# sensors.net
KiCad netlist of a schematic drawn in Altium Designer
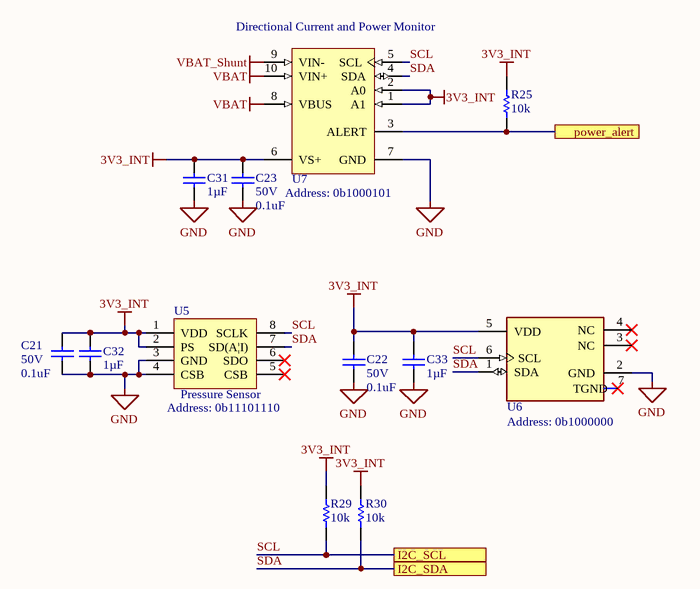
[diagram p0: sensors.SchDoc]

(export (version "E")
  (design (tool "Eeschema 10.0.6"))
  (components
    (comp (ref "C21")
      (value "CL10B104JB8NNNC")
      (footprint "FP-CL10-0_1-MFG")
      (description "CAP CER 0.1UF 50V X7R 0603")
      (fields
        (field (name "TOLERANCE") "5%")
        (field (name "VOLTAGE") "50V")
        (field (name "CAPACITANCE") "0.1uF")
      )
      (libsource (lib "AUVIC") (part "CAP-NP-2"))
    )
    (comp (ref "C22")
      (value "CL10B104JB8NNNC")
      (footprint "FP-CL10-0_1-MFG")
      (description "CAP CER 0.1UF 50V X7R 0603")
      (fields
        (field (name "TOLERANCE") "5%")
        (field (name "VOLTAGE") "50V")
        (field (name "CAPACITANCE") "0.1uF")
      )
      (libsource (lib "AUVIC") (part "CAP-NP-2"))
    )
    (comp (ref "C23")
      (value "CL10B104JB8NNNC")
      (footprint "FP-CL10-0_1-MFG")
      (description "CAP CER 0.1UF 50V X7R 0603")
      (fields
        (field (name "TOLERANCE") "5%")
        (field (name "VOLTAGE") "50V")
        (field (name "CAPACITANCE") "0.1uF")
      )
      (libsource (lib "AUVIC") (part "CAP-NP-2"))
    )
    (comp (ref "C31")
      (value "1µF")
      (footprint "CAPC1608N(0603\")")
      (description "Capacitor, Ceramic, 50V, +/- 10%, 0603 SMD, X5R")
      (fields (field (name "Comment") "1uF 50V 0603 SMD, Ceramic") (field (name "CREATED BY") "Lyden Smith"))
      (libsource (lib "") (part "Symbol_2"))
    )
    (comp (ref "C32")
      (value "1µF")
      (footprint "CAPC1608N(0603\")")
      (description "Capacitor, Ceramic, 50V, +/- 10%, 0603 SMD, X5R")
      (fields (field (name "Comment") "1uF 50V 0603 SMD, Ceramic") (field (name "CREATED BY") "Lyden Smith"))
      (libsource (lib "") (part "Symbol_2"))
    )
    (comp (ref "C33")
      (value "1µF")
      (footprint "CAPC1608N(0603\")")
      (description "Capacitor, Ceramic, 50V, +/- 10%, 0603 SMD, X5R")
      (fields (field (name "Comment") "1uF 50V 0603 SMD, Ceramic") (field (name "CREATED BY") "Lyden Smith"))
      (libsource (lib "") (part "Symbol_2"))
    )
    (comp (ref "R25")
      (value "10k")
      (footprint "RESC1608N(0603\")")
      (description "10kR, 1%, 1/10W, 0603 SMD")
      (fields (field (name "MADE BY") "Ashwin Sira"))
      (libsource (lib "") (part "Symbol_1"))
    )
    (comp (ref "R29")
      (value "10k")
      (footprint "RESC1608N(0603\")")
      (description "10kR, 1%, 1/10W, 0603 SMD")
      (fields (field (name "MADE BY") "Ashwin Sira"))
      (libsource (lib "") (part "Symbol_1"))
    )
    (comp (ref "R30")
      (value "10k")
      (footprint "RESC1608N(0603\")")
      (description "10kR, 1%, 1/10W, 0603 SMD")
      (fields (field (name "MADE BY") "Ashwin Sira"))
      (libsource (lib "") (part "Symbol_1"))
    )
    (comp (ref "U5")
      (value "Pressure Sensor")
      (footprint "TE Pressure Sensor (MS560702BA03-50)")
      (description "1kPa to 120 kPa")
      (fields (field (name "MADE BY") "Andy Bates"))
      (libsource (lib "AUVIC") (part "Symbol"))
    )
    (comp (ref "U6")
      (value "Si700XX")
      (footprint "FP-SI7021-A20-GM1R-IPC_B")
      (description "I2C Humidity and Temperature Sensor")
      (fields (field (name "MADE BY") "Andy Bates"))
      (libsource (lib "AUVIC") (part "36455d3ff5c6bb8356ed7793d24217b"))
    )
    (comp (ref "U7")
      (value "Directional Current and Power Monitor")
      (footprint "DGS0010A_L")
      (description "Bi Directional Current and Power Monitor 10-Pin VSSOP T/R")
      (libsource (lib "AUVIC") (part "TI-INA226DGS10"))
    )
  )
  (nets
    (net (code "1") (name "/SCL") (class "Default")
      (node (ref "R29") (pin "1") (pinfunction "1_1") (pintype "passive"))
      (node (ref "U5") (pin "8") (pinfunction "SCLK_8") (pintype "passive"))
      (node (ref "U6") (pin "6") (pinfunction "SCL_6") (pintype "input"))
      (node (ref "U7") (pin "5") (pinfunction "SCL_5") (pintype "input"))
    )
    (net (code "2") (name "/SDA") (class "Default")
      (node (ref "R30") (pin "1") (pinfunction "1_1") (pintype "passive"))
      (node (ref "U5") (pin "7") (pinfunction "SD(A¦I)_7") (pintype "passive"))
      (node (ref "U6") (pin "1") (pinfunction "SDA_1") (pintype "bidirectional"))
      (node (ref "U7") (pin "4") (pinfunction "SDA_4") (pintype "bidirectional"))
    )
    (net (code "3") (name "/power_alert") (class "Default")
      (node (ref "R25") (pin "1") (pinfunction "1_1") (pintype "passive"))
      (node (ref "U7") (pin "3") (pinfunction "ALERT_3") (pintype "open_collector"))
    )
    (net (code "4") (name "3V3_INT") (class "Default")
      (node (ref "C21") (pin "2") (pinfunction "2_2") (pintype "passive"))
      (node (ref "C22") (pin "2") (pinfunction "2_2") (pintype "passive"))
      (node (ref "C23") (pin "2") (pinfunction "2_2") (pintype "passive"))
      (node (ref "C31") (pin "2") (pinfunction "Cathode_2") (pintype "passive"))
      (node (ref "C32") (pin "2") (pinfunction "Cathode_2") (pintype "passive"))
      (node (ref "C33") (pin "2") (pinfunction "Cathode_2") (pintype "passive"))
      (node (ref "R25") (pin "2") (pinfunction "2_2") (pintype "passive"))
      (node (ref "R29") (pin "2") (pinfunction "2_2") (pintype "passive"))
      (node (ref "R30") (pin "2") (pinfunction "2_2") (pintype "passive"))
      (node (ref "U5") (pin "1") (pinfunction "VDD_1") (pintype "passive"))
      (node (ref "U5") (pin "2") (pinfunction "PS_2") (pintype "passive"))
      (node (ref "U6") (pin "5") (pinfunction "VDD_5") (pintype "power_in"))
      (node (ref "U7") (pin "1") (pinfunction "A1_1") (pintype "input"))
      (node (ref "U7") (pin "2") (pinfunction "A0_2") (pintype "input"))
      (node (ref "U7") (pin "6") (pinfunction "VS+_6") (pintype "power_in"))
    )
    (net (code "5") (name "GND") (class "Default")
      (node (ref "C21") (pin "1") (pinfunction "1_1") (pintype "passive"))
      (node (ref "C22") (pin "1") (pinfunction "1_1") (pintype "passive"))
      (node (ref "C23") (pin "1") (pinfunction "1_1") (pintype "passive"))
      (node (ref "C31") (pin "1") (pinfunction "Anode_1") (pintype "passive"))
      (node (ref "C32") (pin "1") (pinfunction "Anode_1") (pintype "passive"))
      (node (ref "C33") (pin "1") (pinfunction "Anode_1") (pintype "passive"))
      (node (ref "U5") (pin "3") (pinfunction "GND_3") (pintype "passive"))
      (node (ref "U5") (pin "4") (pinfunction "CSB_4") (pintype "passive"))
      (node (ref "U6") (pin "2") (pinfunction "GND_2") (pintype "power_in"))
      (node (ref "U7") (pin "7") (pinfunction "GND_7") (pintype "power_in"))
    )
    (net (code "6") (name "VBAT") (class "Default")
      (node (ref "U7") (pin "10") (pinfunction "VIN+_10") (pintype "input"))
      (node (ref "U7") (pin "8") (pinfunction "VBUS_8") (pintype "input"))
    )
    (net (code "7") (name "VBAT_Shunt") (class "Default")
      (node (ref "U7") (pin "9") (pinfunction "VIN-_9") (pintype "input"))
    )
    (net (code "8") (name "unconnected-(U5-CSB-Pad5)") (class "Default")
      (node (ref "U5") (pin "5") (pinfunction "CSB_5") (pintype "passive+no_connect"))
    )
    (net (code "9") (name "unconnected-(U5-SDO-Pad6)") (class "Default")
      (node (ref "U5") (pin "6") (pinfunction "SDO_6") (pintype "passive+no_connect"))
    )
    (net (code "10") (name "unconnected-(U6-NC-Pad3)") (class "Default")
      (node (ref "U6") (pin "3") (pinfunction "NC_3") (pintype "passive+no_connect"))
    )
    (net (code "11") (name "unconnected-(U6-NC-Pad4)") (class "Default")
      (node (ref "U6") (pin "4") (pinfunction "NC_4") (pintype "passive+no_connect"))
    )
    (net (code "12") (name "unconnected-(U6-TGND-Pad7)") (class "Default")
      (node (ref "U6") (pin "7") (pinfunction "TGND_7") (pintype "power_in+no_connect"))
    )
  )
)
